# internship_emu.net
KiCad netlist of a schematic drawn in EAGLE
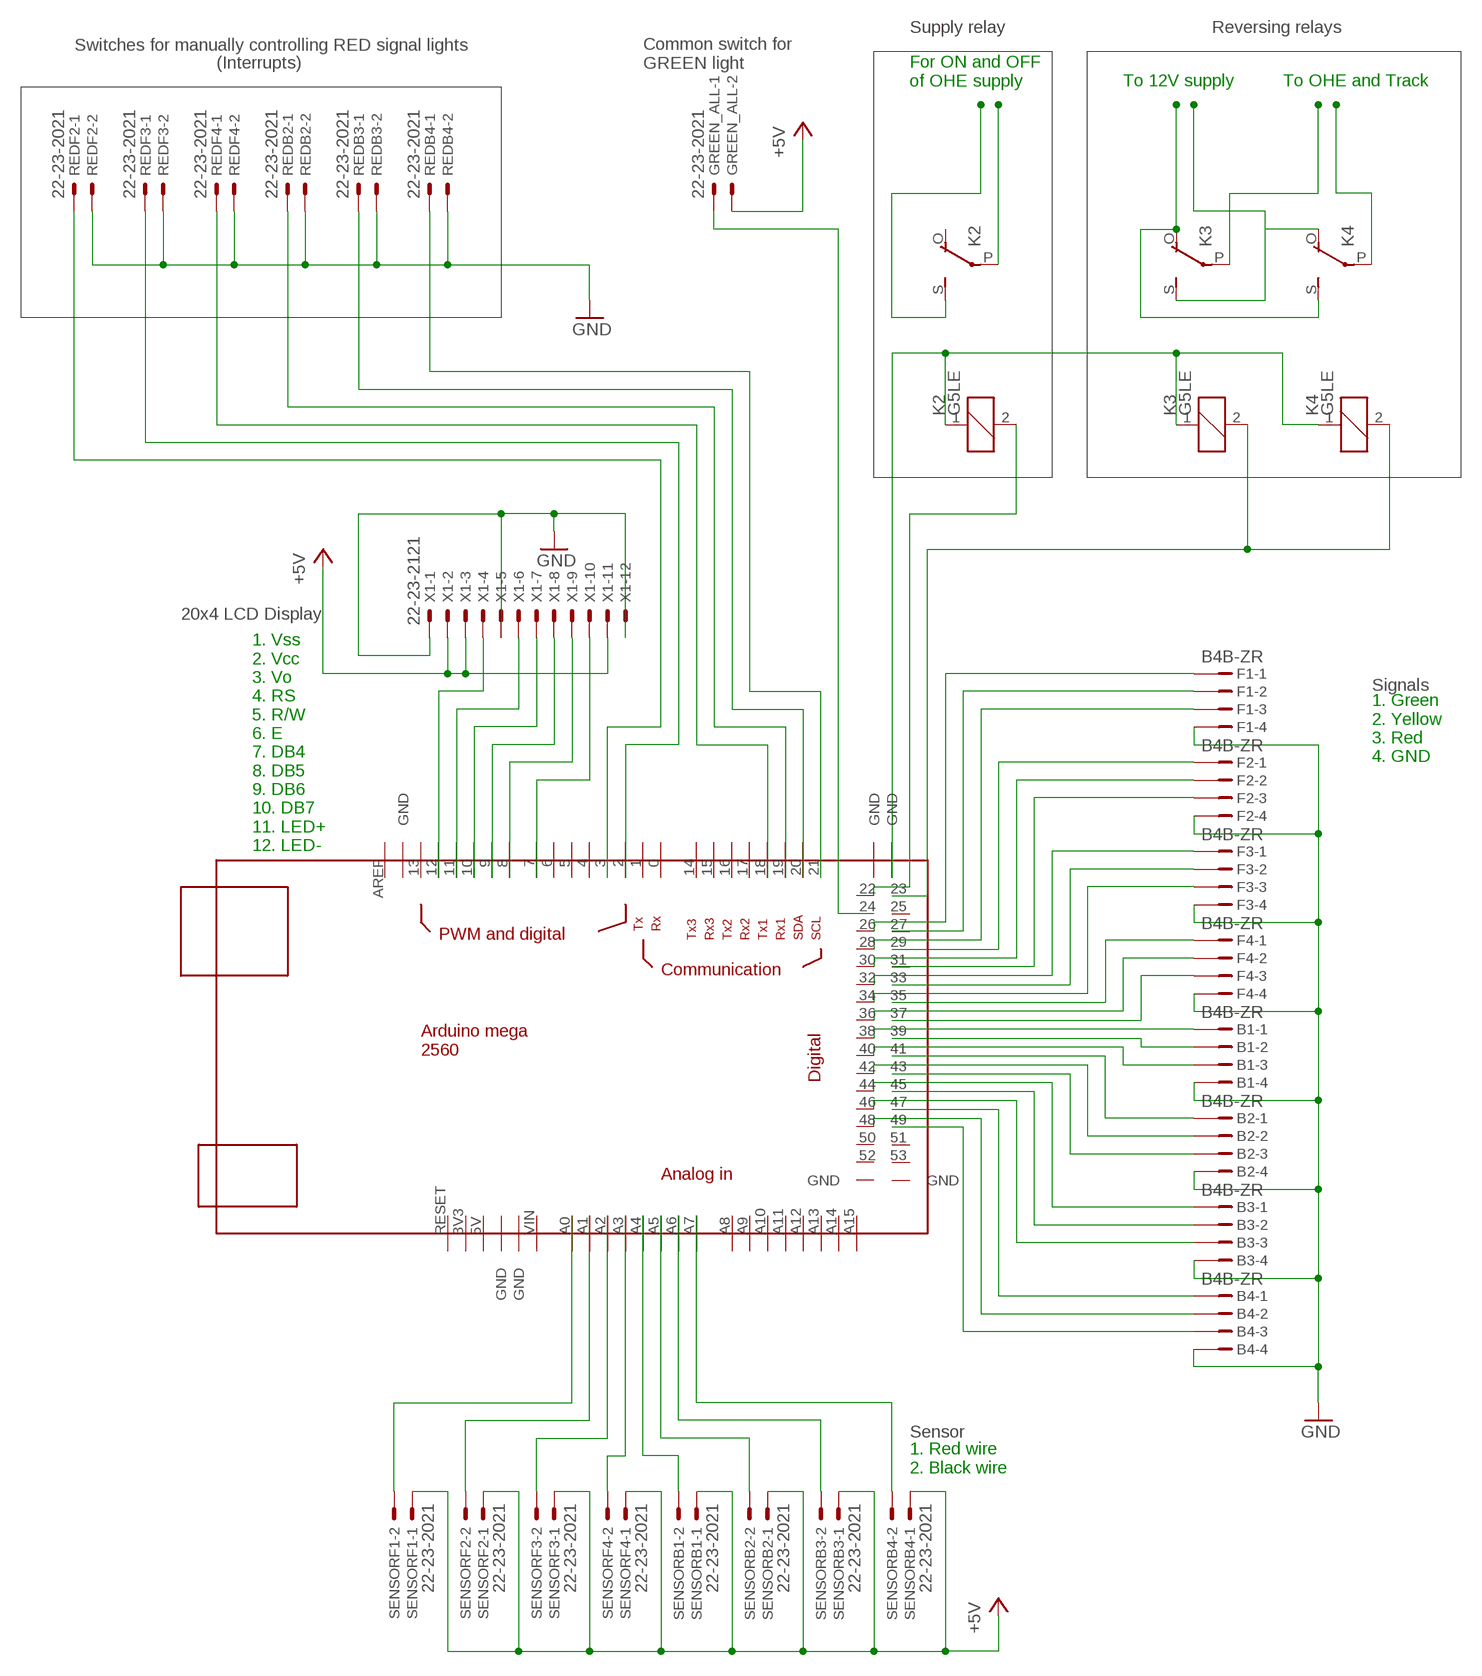
[diagram p0: schematic, sheet 1]

(export (version "E")
  (design (tool "Eeschema 10.0.6"))
  (components
    (comp (ref "B1")
      (value "B4B-ZR")
      (footprint "eagle-import:B4B-ZR")
      (fields (field (name "MF") "FARNELL") (field (name "MPN") "B4B-ZR(LF)(SN)"))
      (libsource (lib "eagle-import") (part "?4B-ZRB"))
    )
    (comp (ref "B2")
      (value "B4B-ZR")
      (footprint "eagle-import:B4B-ZR")
      (fields (field (name "MF") "FARNELL") (field (name "MPN") "B4B-ZR(LF)(SN)"))
      (libsource (lib "eagle-import") (part "?4B-ZRB"))
    )
    (comp (ref "B3")
      (value "B4B-ZR")
      (footprint "eagle-import:B4B-ZR")
      (fields (field (name "MF") "FARNELL") (field (name "MPN") "B4B-ZR(LF)(SN)"))
      (libsource (lib "eagle-import") (part "?4B-ZRB"))
    )
    (comp (ref "B4")
      (value "B4B-ZR")
      (footprint "eagle-import:B4B-ZR")
      (fields (field (name "MF") "FARNELL") (field (name "MPN") "B4B-ZR(LF)(SN)"))
      (libsource (lib "eagle-import") (part "?4B-ZRB"))
    )
    (comp (ref "F1")
      (value "B4B-ZR")
      (footprint "eagle-import:B4B-ZR")
      (fields (field (name "MF") "FARNELL") (field (name "MPN") "B4B-ZR(LF)(SN)"))
      (libsource (lib "eagle-import") (part "?4B-ZRB"))
    )
    (comp (ref "F2")
      (value "B4B-ZR")
      (footprint "eagle-import:B4B-ZR")
      (fields (field (name "MF") "FARNELL") (field (name "MPN") "B4B-ZR(LF)(SN)"))
      (libsource (lib "eagle-import") (part "?4B-ZRB"))
    )
    (comp (ref "F3")
      (value "B4B-ZR")
      (footprint "eagle-import:B4B-ZR")
      (fields (field (name "MF") "FARNELL") (field (name "MPN") "B4B-ZR(LF)(SN)"))
      (libsource (lib "eagle-import") (part "?4B-ZRB"))
    )
    (comp (ref "F4")
      (value "B4B-ZR")
      (footprint "eagle-import:B4B-ZR")
      (fields (field (name "MF") "FARNELL") (field (name "MPN") "B4B-ZR(LF)(SN)"))
      (libsource (lib "eagle-import") (part "?4B-ZRB"))
    )
    (comp (ref "GREEN_ALL")
      (value "22-23-2021")
      (footprint "eagle-import:22-23-2021")
      (fields (field (name "MF") "MOLEX"))
      (libsource (lib "eagle-import") (part "22-23-2021"))
    )
    (comp (ref "K2")
      (value "G5LE")
      (footprint "eagle-import:G5LE")
      (libsource (lib "eagle-import") (part "G5LE"))
    )
    (comp (ref "K3")
      (value "G5LE")
      (footprint "eagle-import:G5LE")
      (libsource (lib "eagle-import") (part "G5LE"))
    )
    (comp (ref "K4")
      (value "G5LE")
      (footprint "eagle-import:G5LE")
      (libsource (lib "eagle-import") (part "G5LE"))
    )
    (comp (ref "REDB2")
      (value "22-23-2021")
      (footprint "eagle-import:22-23-2021")
      (fields (field (name "MF") "MOLEX"))
      (libsource (lib "eagle-import") (part "22-23-2021"))
    )
    (comp (ref "REDB3")
      (value "22-23-2021")
      (footprint "eagle-import:22-23-2021")
      (fields (field (name "MF") "MOLEX"))
      (libsource (lib "eagle-import") (part "22-23-2021"))
    )
    (comp (ref "REDB4")
      (value "22-23-2021")
      (footprint "eagle-import:22-23-2021")
      (fields (field (name "MF") "MOLEX"))
      (libsource (lib "eagle-import") (part "22-23-2021"))
    )
    (comp (ref "REDF2")
      (value "22-23-2021")
      (footprint "eagle-import:22-23-2021")
      (fields (field (name "MF") "MOLEX"))
      (libsource (lib "eagle-import") (part "22-23-2021"))
    )
    (comp (ref "REDF3")
      (value "22-23-2021")
      (footprint "eagle-import:22-23-2021")
      (fields (field (name "MF") "MOLEX"))
      (libsource (lib "eagle-import") (part "22-23-2021"))
    )
    (comp (ref "REDF4")
      (value "22-23-2021")
      (footprint "eagle-import:22-23-2021")
      (fields (field (name "MF") "MOLEX"))
      (libsource (lib "eagle-import") (part "22-23-2021"))
    )
    (comp (ref "SENSORB1")
      (value "22-23-2021")
      (footprint "eagle-import:22-23-2021")
      (fields (field (name "MF") "MOLEX"))
      (libsource (lib "eagle-import") (part "22-23-2021"))
    )
    (comp (ref "SENSORB2")
      (value "22-23-2021")
      (footprint "eagle-import:22-23-2021")
      (fields (field (name "MF") "MOLEX"))
      (libsource (lib "eagle-import") (part "22-23-2021"))
    )
    (comp (ref "SENSORB3")
      (value "22-23-2021")
      (footprint "eagle-import:22-23-2021")
      (fields (field (name "MF") "MOLEX"))
      (libsource (lib "eagle-import") (part "22-23-2021"))
    )
    (comp (ref "SENSORB4")
      (value "22-23-2021")
      (footprint "eagle-import:22-23-2021")
      (fields (field (name "MF") "MOLEX"))
      (libsource (lib "eagle-import") (part "22-23-2021"))
    )
    (comp (ref "SENSORF1")
      (value "22-23-2021")
      (footprint "eagle-import:22-23-2021")
      (fields (field (name "MF") "MOLEX"))
      (libsource (lib "eagle-import") (part "22-23-2021"))
    )
    (comp (ref "SENSORF2")
      (value "22-23-2021")
      (footprint "eagle-import:22-23-2021")
      (fields (field (name "MF") "MOLEX"))
      (libsource (lib "eagle-import") (part "22-23-2021"))
    )
    (comp (ref "SENSORF3")
      (value "22-23-2021")
      (footprint "eagle-import:22-23-2021")
      (fields (field (name "MF") "MOLEX"))
      (libsource (lib "eagle-import") (part "22-23-2021"))
    )
    (comp (ref "SENSORF4")
      (value "22-23-2021")
      (footprint "eagle-import:22-23-2021")
      (fields (field (name "MF") "MOLEX"))
      (libsource (lib "eagle-import") (part "22-23-2021"))
    )
    (comp (ref "U$1")
      (value "MEGA_DEVICE")
      (footprint "eagle-import:MEGAOUTLINE")
      (libsource (lib "eagle-import") (part "MEGA_DEVICE"))
    )
    (comp (ref "X1")
      (value "22-23-2121")
      (footprint "eagle-import:22-23-2121")
      (fields (field (name "MF") "MOLEX"))
      (libsource (lib "eagle-import") (part "22-23-2121"))
    )
  )
  (nets
    (net (code "1") (name "+5V") (class "Default")
      (node (ref "GREEN_ALL") (pin "2") (pinfunction "S_2") (pintype "passive"))
      (node (ref "SENSORB1") (pin "1") (pinfunction "S_1") (pintype "passive"))
      (node (ref "SENSORB2") (pin "1") (pinfunction "S_1") (pintype "passive"))
      (node (ref "SENSORB3") (pin "1") (pinfunction "S_1") (pintype "passive"))
      (node (ref "SENSORB4") (pin "1") (pinfunction "S_1") (pintype "passive"))
      (node (ref "SENSORF1") (pin "1") (pinfunction "S_1") (pintype "passive"))
      (node (ref "SENSORF2") (pin "1") (pinfunction "S_1") (pintype "passive"))
      (node (ref "SENSORF3") (pin "1") (pinfunction "S_1") (pintype "passive"))
      (node (ref "SENSORF4") (pin "1") (pinfunction "S_1") (pintype "passive"))
      (node (ref "X1") (pin "11") (pinfunction "S_11") (pintype "passive"))
      (node (ref "X1") (pin "2") (pinfunction "S_2") (pintype "passive"))
      (node (ref "X1") (pin "3") (pinfunction "S_3") (pintype "passive"))
    )
    (net (code "2") (name "GND") (class "Default")
      (node (ref "B1") (pin "4") (pinfunction "1_4") (pintype "passive"))
      (node (ref "B2") (pin "4") (pinfunction "1_4") (pintype "passive"))
      (node (ref "B3") (pin "4") (pinfunction "1_4") (pintype "passive"))
      (node (ref "B4") (pin "4") (pinfunction "1_4") (pintype "passive"))
      (node (ref "F1") (pin "4") (pinfunction "1_4") (pintype "passive"))
      (node (ref "F2") (pin "4") (pinfunction "1_4") (pintype "passive"))
      (node (ref "F3") (pin "4") (pinfunction "1_4") (pintype "passive"))
      (node (ref "F4") (pin "4") (pinfunction "1_4") (pintype "passive"))
      (node (ref "REDB2") (pin "2") (pinfunction "S_2") (pintype "passive"))
      (node (ref "REDB3") (pin "2") (pinfunction "S_2") (pintype "passive"))
      (node (ref "REDB4") (pin "2") (pinfunction "S_2") (pintype "passive"))
      (node (ref "REDF2") (pin "2") (pinfunction "S_2") (pintype "passive"))
      (node (ref "REDF3") (pin "2") (pinfunction "S_2") (pintype "passive"))
      (node (ref "REDF4") (pin "2") (pinfunction "S_2") (pintype "passive"))
      (node (ref "X1") (pin "1") (pinfunction "S_1") (pintype "passive"))
      (node (ref "X1") (pin "12") (pinfunction "S_12") (pintype "passive"))
      (node (ref "X1") (pin "5") (pinfunction "S_5") (pintype "passive"))
    )
    (net (code "3") (name "Net-(B1-Pad1)") (class "Default")
      (node (ref "B1") (pin "1") (pinfunction "1_1") (pintype "passive"))
      (node (ref "U$1") (pin "38") (pinfunction "38_38") (pintype "bidirectional"))
    )
    (net (code "4") (name "Net-(B1B-1)") (class "Default")
      (node (ref "B1") (pin "2") (pinfunction "1_2") (pintype "passive"))
      (node (ref "U$1") (pin "39") (pinfunction "39_39") (pintype "bidirectional"))
    )
    (net (code "5") (name "Net-(B1C-1)") (class "Default")
      (node (ref "B1") (pin "3") (pinfunction "1_3") (pintype "passive"))
      (node (ref "U$1") (pin "40") (pinfunction "40_40") (pintype "bidirectional"))
    )
    (net (code "6") (name "Net-(B2-Pad1)") (class "Default")
      (node (ref "B2") (pin "1") (pinfunction "1_1") (pintype "passive"))
      (node (ref "U$1") (pin "41") (pinfunction "41_41") (pintype "bidirectional"))
    )
    (net (code "7") (name "Net-(B2B-1)") (class "Default")
      (node (ref "B2") (pin "2") (pinfunction "1_2") (pintype "passive"))
      (node (ref "U$1") (pin "42") (pinfunction "42_42") (pintype "bidirectional"))
    )
    (net (code "8") (name "Net-(B2C-1)") (class "Default")
      (node (ref "B2") (pin "3") (pinfunction "1_3") (pintype "passive"))
      (node (ref "U$1") (pin "43") (pinfunction "43_43") (pintype "bidirectional"))
    )
    (net (code "9") (name "Net-(B3-Pad1)") (class "Default")
      (node (ref "B3") (pin "1") (pinfunction "1_1") (pintype "passive"))
      (node (ref "U$1") (pin "44") (pinfunction "44_44") (pintype "bidirectional"))
    )
    (net (code "10") (name "Net-(B3B-1)") (class "Default")
      (node (ref "B3") (pin "2") (pinfunction "1_2") (pintype "passive"))
      (node (ref "U$1") (pin "45") (pinfunction "45_45") (pintype "bidirectional"))
    )
    (net (code "11") (name "Net-(B3C-1)") (class "Default")
      (node (ref "B3") (pin "3") (pinfunction "1_3") (pintype "passive"))
      (node (ref "U$1") (pin "46") (pinfunction "46_46") (pintype "bidirectional"))
    )
    (net (code "12") (name "Net-(B4-Pad1)") (class "Default")
      (node (ref "B4") (pin "1") (pinfunction "1_1") (pintype "passive"))
      (node (ref "U$1") (pin "47") (pinfunction "47_47") (pintype "bidirectional"))
    )
    (net (code "13") (name "Net-(B4B-1)") (class "Default")
      (node (ref "B4") (pin "2") (pinfunction "1_2") (pintype "passive"))
      (node (ref "U$1") (pin "48") (pinfunction "48_48") (pintype "bidirectional"))
    )
    (net (code "14") (name "Net-(B4C-1)") (class "Default")
      (node (ref "B4") (pin "3") (pinfunction "1_3") (pintype "passive"))
      (node (ref "U$1") (pin "49") (pinfunction "49_49") (pintype "bidirectional"))
    )
    (net (code "15") (name "Net-(F1-Pad1)") (class "Default")
      (node (ref "F1") (pin "1") (pinfunction "1_1") (pintype "passive"))
      (node (ref "U$1") (pin "26") (pinfunction "26_26") (pintype "bidirectional"))
    )
    (net (code "16") (name "Net-(F1B-1)") (class "Default")
      (node (ref "F1") (pin "2") (pinfunction "1_2") (pintype "passive"))
      (node (ref "U$1") (pin "27") (pinfunction "27_27") (pintype "bidirectional"))
    )
    (net (code "17") (name "Net-(F1C-1)") (class "Default")
      (node (ref "F1") (pin "3") (pinfunction "1_3") (pintype "passive"))
      (node (ref "U$1") (pin "28") (pinfunction "28_28") (pintype "bidirectional"))
    )
    (net (code "18") (name "Net-(F2-Pad1)") (class "Default")
      (node (ref "F2") (pin "1") (pinfunction "1_1") (pintype "passive"))
      (node (ref "U$1") (pin "29") (pinfunction "29_29") (pintype "bidirectional"))
    )
    (net (code "19") (name "Net-(F2B-1)") (class "Default")
      (node (ref "F2") (pin "2") (pinfunction "1_2") (pintype "passive"))
      (node (ref "U$1") (pin "30") (pinfunction "30_30") (pintype "bidirectional"))
    )
    (net (code "20") (name "Net-(F2C-1)") (class "Default")
      (node (ref "F2") (pin "3") (pinfunction "1_3") (pintype "passive"))
      (node (ref "U$1") (pin "31") (pinfunction "31_31") (pintype "bidirectional"))
    )
    (net (code "21") (name "Net-(F3-Pad1)") (class "Default")
      (node (ref "F3") (pin "1") (pinfunction "1_1") (pintype "passive"))
      (node (ref "U$1") (pin "32") (pinfunction "32_32") (pintype "bidirectional"))
    )
    (net (code "22") (name "Net-(F3B-1)") (class "Default")
      (node (ref "F3") (pin "2") (pinfunction "1_2") (pintype "passive"))
      (node (ref "U$1") (pin "33") (pinfunction "33_33") (pintype "bidirectional"))
    )
    (net (code "23") (name "Net-(F3C-1)") (class "Default")
      (node (ref "F3") (pin "3") (pinfunction "1_3") (pintype "passive"))
      (node (ref "U$1") (pin "34") (pinfunction "34_34") (pintype "bidirectional"))
    )
    (net (code "24") (name "Net-(F4-Pad1)") (class "Default")
      (node (ref "F4") (pin "1") (pinfunction "1_1") (pintype "passive"))
      (node (ref "U$1") (pin "35") (pinfunction "35_35") (pintype "bidirectional"))
    )
    (net (code "25") (name "Net-(F4B-1)") (class "Default")
      (node (ref "F4") (pin "2") (pinfunction "1_2") (pintype "passive"))
      (node (ref "U$1") (pin "36") (pinfunction "36_36") (pintype "bidirectional"))
    )
    (net (code "26") (name "Net-(F4C-1)") (class "Default")
      (node (ref "F4") (pin "3") (pinfunction "1_3") (pintype "passive"))
      (node (ref "U$1") (pin "37") (pinfunction "37_37") (pintype "bidirectional"))
    )
    (net (code "27") (name "Net-(GREEN_ALLA-S)") (class "Default")
      (node (ref "GREEN_ALL") (pin "1") (pinfunction "S_1") (pintype "passive"))
      (node (ref "U$1") (pin "24") (pinfunction "24_24") (pintype "bidirectional"))
    )
    (net (code "28") (name "Net-(K2-Pad1)") (class "Default")
      (node (ref "K2") (pin "1") (pinfunction "1_1") (pintype "passive"))
      (node (ref "K3") (pin "1") (pinfunction "1_1") (pintype "passive"))
      (node (ref "K4") (pin "1") (pinfunction "1_1") (pintype "passive"))
      (node (ref "U$1") (pin "GND@5") (pinfunction "GND_GND@5") (pintype "bidirectional"))
    )
    (net (code "29") (name "Net-(K2-Pad2)") (class "Default")
      (node (ref "K2") (pin "2") (pinfunction "2_2") (pintype "passive"))
      (node (ref "U$1") (pin "22") (pinfunction "22_22") (pintype "bidirectional"))
    )
    (net (code "30") (name "Net-(K3-Pad2)") (class "Default")
      (node (ref "K3") (pin "2") (pinfunction "2_2") (pintype "passive"))
      (node (ref "K4") (pin "2") (pinfunction "2_2") (pintype "passive"))
      (node (ref "U$1") (pin "23") (pinfunction "23_23") (pintype "bidirectional"))
    )
    (net (code "31") (name "Net-(K3-PadO)") (class "Default")
      (node (ref "K3") (pin "O") (pinfunction "O_O") (pintype "passive"))
      (node (ref "K4") (pin "S") (pinfunction "S_S") (pintype "passive"))
    )
    (net (code "32") (name "Net-(K3-PadS)") (class "Default")
      (node (ref "K3") (pin "S") (pinfunction "S_S") (pintype "passive"))
      (node (ref "K4") (pin "O") (pinfunction "O_O") (pintype "passive"))
    )
    (net (code "33") (name "Net-(REDB2A-S)") (class "Default")
      (node (ref "REDB2") (pin "1") (pinfunction "S_1") (pintype "passive"))
      (node (ref "U$1") (pin "19") (pinfunction "19_19") (pintype "bidirectional"))
    )
    (net (code "34") (name "Net-(REDB3A-S)") (class "Default")
      (node (ref "REDB3") (pin "1") (pinfunction "S_1") (pintype "passive"))
      (node (ref "U$1") (pin "20") (pinfunction "20_20") (pintype "bidirectional"))
    )
    (net (code "35") (name "Net-(REDB4A-S)") (class "Default")
      (node (ref "REDB4") (pin "1") (pinfunction "S_1") (pintype "passive"))
      (node (ref "U$1") (pin "21") (pinfunction "21_21") (pintype "bidirectional"))
    )
    (net (code "36") (name "Net-(REDF2A-S)") (class "Default")
      (node (ref "REDF2") (pin "1") (pinfunction "S_1") (pintype "passive"))
      (node (ref "U$1") (pin "3") (pinfunction "3_3") (pintype "bidirectional"))
    )
    (net (code "37") (name "Net-(REDF3A-S)") (class "Default")
      (node (ref "REDF3") (pin "1") (pinfunction "S_1") (pintype "passive"))
      (node (ref "U$1") (pin "2") (pinfunction "2_2") (pintype "bidirectional"))
    )
    (net (code "38") (name "Net-(REDF4A-S)") (class "Default")
      (node (ref "REDF4") (pin "1") (pinfunction "S_1") (pintype "passive"))
      (node (ref "U$1") (pin "18") (pinfunction "18_18") (pintype "bidirectional"))
    )
    (net (code "39") (name "Net-(SENSORB1B-S)") (class "Default")
      (node (ref "SENSORB1") (pin "2") (pinfunction "S_2") (pintype "passive"))
      (node (ref "U$1") (pin "A4") (pinfunction "A4_A4") (pintype "bidirectional"))
    )
    (net (code "40") (name "Net-(SENSORB2B-S)") (class "Default")
      (node (ref "SENSORB2") (pin "2") (pinfunction "S_2") (pintype "passive"))
      (node (ref "U$1") (pin "A5") (pinfunction "A5_A5") (pintype "bidirectional"))
    )
    (net (code "41") (name "Net-(SENSORB3B-S)") (class "Default")
      (node (ref "SENSORB3") (pin "2") (pinfunction "S_2") (pintype "passive"))
      (node (ref "U$1") (pin "A6") (pinfunction "A6_A6") (pintype "bidirectional"))
    )
    (net (code "42") (name "Net-(SENSORB4B-S)") (class "Default")
      (node (ref "SENSORB4") (pin "2") (pinfunction "S_2") (pintype "passive"))
      (node (ref "U$1") (pin "A7") (pinfunction "A7_A7") (pintype "bidirectional"))
    )
    (net (code "43") (name "Net-(SENSORF1B-S)") (class "Default")
      (node (ref "SENSORF1") (pin "2") (pinfunction "S_2") (pintype "passive"))
      (node (ref "U$1") (pin "A0") (pinfunction "A0_A0") (pintype "bidirectional"))
    )
    (net (code "44") (name "Net-(SENSORF2B-S)") (class "Default")
      (node (ref "SENSORF2") (pin "2") (pinfunction "S_2") (pintype "passive"))
      (node (ref "U$1") (pin "A1") (pinfunction "A1_A1") (pintype "bidirectional"))
    )
    (net (code "45") (name "Net-(SENSORF3B-S)") (class "Default")
      (node (ref "SENSORF3") (pin "2") (pinfunction "S_2") (pintype "passive"))
      (node (ref "U$1") (pin "A2") (pinfunction "A2_A2") (pintype "bidirectional"))
    )
    (net (code "46") (name "Net-(SENSORF4B-S)") (class "Default")
      (node (ref "SENSORF4") (pin "2") (pinfunction "S_2") (pintype "passive"))
      (node (ref "U$1") (pin "A3") (pinfunction "A3_A3") (pintype "bidirectional"))
    )
    (net (code "47") (name "Net-(X1B-S)") (class "Default")
      (node (ref "U$1") (pin "7") (pinfunction "7_7") (pintype "bidirectional"))
      (node (ref "X1") (pin "10") (pinfunction "S_10") (pintype "passive"))
    )
    (net (code "48") (name "Net-(X1G-S)") (class "Default")
      (node (ref "U$1") (pin "12") (pinfunction "12_12") (pintype "bidirectional"))
      (node (ref "X1") (pin "4") (pinfunction "S_4") (pintype "passive"))
    )
    (net (code "49") (name "Net-(X1I-S)") (class "Default")
      (node (ref "U$1") (pin "11") (pinfunction "11_11") (pintype "bidirectional"))
      (node (ref "X1") (pin "6") (pinfunction "S_6") (pintype "passive"))
    )
    (net (code "50") (name "Net-(X1J-S)") (class "Default")
      (node (ref "U$1") (pin "10") (pinfunction "10_10") (pintype "bidirectional"))
      (node (ref "X1") (pin "7") (pinfunction "S_7") (pintype "passive"))
    )
    (net (code "51") (name "Net-(X1K-S)") (class "Default")
      (node (ref "U$1") (pin "9") (pinfunction "9_9") (pintype "bidirectional"))
      (node (ref "X1") (pin "8") (pinfunction "S_8") (pintype "passive"))
    )
    (net (code "52") (name "Net-(X1L-S)") (class "Default")
      (node (ref "U$1") (pin "8") (pinfunction "8_8") (pintype "bidirectional"))
      (node (ref "X1") (pin "9") (pinfunction "S_9") (pintype "passive"))
    )
    (net (code "53") (name "unconnected-(K2-PadO)") (class "Default")
      (node (ref "K2") (pin "O") (pinfunction "O_O") (pintype "passive"))
    )
    (net (code "54") (name "unconnected-(K2-PadP)") (class "Default")
      (node (ref "K2") (pin "P") (pinfunction "P_P") (pintype "passive"))
    )
    (net (code "55") (name "unconnected-(K2-PadS)") (class "Default")
      (node (ref "K2") (pin "S") (pinfunction "S_S") (pintype "passive"))
    )
    (net (code "56") (name "unconnected-(K3-PadP)") (class "Default")
      (node (ref "K3") (pin "P") (pinfunction "P_P") (pintype "passive"))
    )
    (net (code "57") (name "unconnected-(K4-PadP)") (class "Default")
      (node (ref "K4") (pin "P") (pinfunction "P_P") (pintype "passive"))
    )
    (net (code "58") (name "unconnected-(U$1-GND-PadGND@1)") (class "Default")
      (node (ref "U$1") (pin "GND@1") (pinfunction "GND_GND@1") (pintype "bidirectional"))
    )
    (net (code "59") (name "unconnected-(U$1-GND-PadGND@2)") (class "Default")
      (node (ref "U$1") (pin "GND@2") (pinfunction "GND_GND@2") (pintype "bidirectional"))
    )
    (net (code "60") (name "unconnected-(U$1-GND-PadGND@3)") (class "Default")
      (node (ref "U$1") (pin "GND@3") (pinfunction "GND_GND@3") (pintype "bidirectional"))
    )
    (net (code "61") (name "unconnected-(U$1-GND-PadGND@4)") (class "Default")
      (node (ref "U$1") (pin "GND@4") (pinfunction "GND_GND@4") (pintype "bidirectional"))
    )
    (net (code "62") (name "unconnected-(U$1-GND-PadGND@6)") (class "Default")
      (node (ref "U$1") (pin "GND@6") (pinfunction "GND_GND@6") (pintype "bidirectional"))
    )
    (net (code "63") (name "unconnected-(U$1-GND-PadGND@7)") (class "Default")
      (node (ref "U$1") (pin "GND@7") (pinfunction "GND_GND@7") (pintype "bidirectional"))
    )
    (net (code "64") (name "unconnected-(U$1-Pad0)") (class "Default")
      (node (ref "U$1") (pin "0") (pinfunction "0_0") (pintype "bidirectional"))
    )
    (net (code "65") (name "unconnected-(U$1-Pad1)") (class "Default")
      (node (ref "U$1") (pin "1") (pinfunction "1_1") (pintype "bidirectional"))
    )
    (net (code "66") (name "unconnected-(U$1-Pad3V3)") (class "Default")
      (node (ref "U$1") (pin "3V3") (pinfunction "3V3_3V3") (pintype "bidirectional"))
    )
    (net (code "67") (name "unconnected-(U$1-Pad4)") (class "Default")
      (node (ref "U$1") (pin "4") (pinfunction "4_4") (pintype "bidirectional"))
    )
    (net (code "68") (name "unconnected-(U$1-Pad5)") (class "Default")
      (node (ref "U$1") (pin "5") (pinfunction "5_5") (pintype "bidirectional"))
    )
    (net (code "69") (name "unconnected-(U$1-Pad5V)") (class "Default")
      (node (ref "U$1") (pin "5V") (pinfunction "5V_5V") (pintype "bidirectional"))
    )
    (net (code "70") (name "unconnected-(U$1-Pad6)") (class "Default")
      (node (ref "U$1") (pin "6") (pinfunction "6_6") (pintype "bidirectional"))
    )
    (net (code "71") (name "unconnected-(U$1-Pad13)") (class "Default")
      (node (ref "U$1") (pin "13") (pinfunction "13_13") (pintype "bidirectional"))
    )
    (net (code "72") (name "unconnected-(U$1-Pad14)") (class "Default")
      (node (ref "U$1") (pin "14") (pinfunction "14_14") (pintype "bidirectional"))
    )
    (net (code "73") (name "unconnected-(U$1-Pad15)") (class "Default")
      (node (ref "U$1") (pin "15") (pinfunction "15_15") (pintype "bidirectional"))
    )
    (net (code "74") (name "unconnected-(U$1-Pad16)") (class "Default")
      (node (ref "U$1") (pin "16") (pinfunction "16_16") (pintype "bidirectional"))
    )
    (net (code "75") (name "unconnected-(U$1-Pad17)") (class "Default")
      (node (ref "U$1") (pin "17") (pinfunction "17_17") (pintype "bidirectional"))
    )
    (net (code "76") (name "unconnected-(U$1-Pad25)") (class "Default")
      (node (ref "U$1") (pin "25") (pinfunction "25_25") (pintype "bidirectional"))
    )
    (net (code "77") (name "unconnected-(U$1-Pad50)") (class "Default")
      (node (ref "U$1") (pin "50") (pinfunction "50_50") (pintype "bidirectional"))
    )
    (net (code "78") (name "unconnected-(U$1-Pad51)") (class "Default")
      (node (ref "U$1") (pin "51") (pinfunction "51_51") (pintype "bidirectional"))
    )
    (net (code "79") (name "unconnected-(U$1-Pad52)") (class "Default")
      (node (ref "U$1") (pin "52") (pinfunction "52_52") (pintype "bidirectional"))
    )
    (net (code "80") (name "unconnected-(U$1-Pad53)") (class "Default")
      (node (ref "U$1") (pin "53") (pinfunction "53_53") (pintype "bidirectional"))
    )
    (net (code "81") (name "unconnected-(U$1-PadA8)") (class "Default")
      (node (ref "U$1") (pin "A8") (pinfunction "A8_A8") (pintype "bidirectional"))
    )
    (net (code "82") (name "unconnected-(U$1-PadA9)") (class "Default")
      (node (ref "U$1") (pin "A9") (pinfunction "A9_A9") (pintype "bidirectional"))
    )
    (net (code "83") (name "unconnected-(U$1-PadA10)") (class "Default")
      (node (ref "U$1") (pin "A10") (pinfunction "A10_A10") (pintype "bidirectional"))
    )
    (net (code "84") (name "unconnected-(U$1-PadA11)") (class "Default")
      (node (ref "U$1") (pin "A11") (pinfunction "A11_A11") (pintype "bidirectional"))
    )
    (net (code "85") (name "unconnected-(U$1-PadA12)") (class "Default")
      (node (ref "U$1") (pin "A12") (pinfunction "A12_A12") (pintype "bidirectional"))
    )
    (net (code "86") (name "unconnected-(U$1-PadA13)") (class "Default")
      (node (ref "U$1") (pin "A13") (pinfunction "A13_A13") (pintype "bidirectional"))
    )
    (net (code "87") (name "unconnected-(U$1-PadA14)") (class "Default")
      (node (ref "U$1") (pin "A14") (pinfunction "A14_A14") (pintype "bidirectional"))
    )
    (net (code "88") (name "unconnected-(U$1-PadA15)") (class "Default")
      (node (ref "U$1") (pin "A15") (pinfunction "A15_A15") (pintype "bidirectional"))
    )
    (net (code "89") (name "unconnected-(U$1-PadAREF)") (class "Default")
      (node (ref "U$1") (pin "AREF") (pinfunction "AREF_AREF") (pintype "bidirectional"))
    )
    (net (code "90") (name "unconnected-(U$1-PadRESET)") (class "Default")
      (node (ref "U$1") (pin "RESET") (pinfunction "RESET_RESET") (pintype "bidirectional"))
    )
    (net (code "91") (name "unconnected-(U$1-PadVIN)") (class "Default")
      (node (ref "U$1") (pin "VIN") (pinfunction "VIN_VIN") (pintype "bidirectional"))
    )
  )
)
